# outputs.net
KiCad netlist of a schematic drawn in Altium Designer
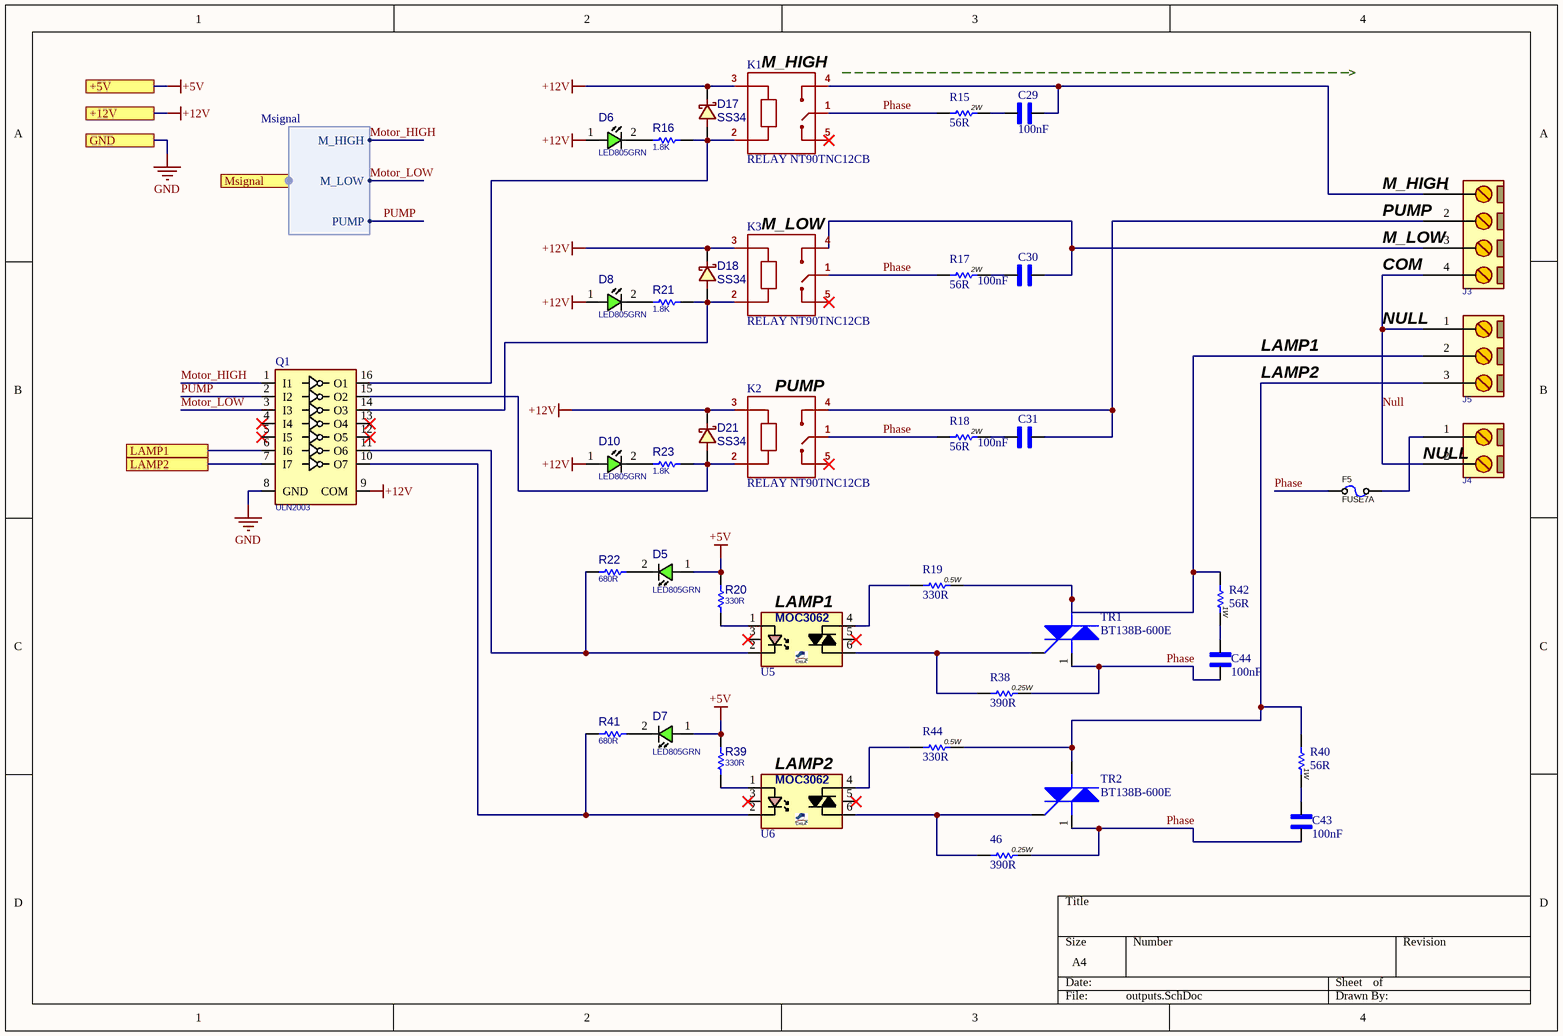
[diagram p0: outputs.SchDoc]

(export (version "E")
  (design (tool "Eeschema 10.0.6"))
  (components
    (comp (ref "46")
      (value "390R")
      (footprint "Res THD 0.25w")
      (description "Resistor 1/4W")
      (libsource (lib "Mehrdad") (part "Res THD 0.25w"))
    )
    (comp (ref "C29")
      (value "100nF")
      (footprint "Capacitor Film")
      (description "Capacitor Film Pitch=10mm")
      (libsource (lib "Mehrdad") (part "Capacitor Film"))
    )
    (comp (ref "C30")
      (value "100nF")
      (footprint "Capacitor Film")
      (description "Capacitor Film Pitch=10mm")
      (libsource (lib "Mehrdad") (part "Capacitor Film"))
    )
    (comp (ref "C31")
      (value "100nF")
      (footprint "Capacitor Film")
      (description "Capacitor Film Pitch=10mm")
      (libsource (lib "Mehrdad") (part "Capacitor Film"))
    )
    (comp (ref "C43")
      (value "100nF")
      (footprint "Capacitor Film")
      (description "Capacitor Film Pitch=10mm")
      (libsource (lib "") (part "Capacitor Film_1"))
    )
    (comp (ref "C44")
      (value "100nF")
      (footprint "Capacitor Film")
      (description "Capacitor Film Pitch=10mm")
      (libsource (lib "") (part "Capacitor Film_1"))
    )
    (comp (ref "D5")
      (value "LED805GRN")
      (footprint "LED0805GRN")
      (description "LED, SMD, 0805, GREEN")
      (libsource (lib "led(diode)") (part "LED_SMD_0805_GRN"))
    )
    (comp (ref "D6")
      (value "LED805GRN")
      (footprint "LED0805GRN")
      (description "LED, SMD, 0805, GREEN")
      (libsource (lib "led(diode)") (part "LED_SMD_0805_GRN"))
    )
    (comp (ref "D7")
      (value "LED805GRN")
      (footprint "LED0805GRN")
      (description "LED, SMD, 0805, GREEN")
      (libsource (lib "led(diode)") (part "LED_SMD_0805_GRN"))
    )
    (comp (ref "D8")
      (value "LED805GRN")
      (footprint "LED0805GRN")
      (description "LED, SMD, 0805, GREEN")
      (libsource (lib "led(diode)") (part "LED_SMD_0805_GRN"))
    )
    (comp (ref "D10")
      (value "LED805GRN")
      (footprint "LED0805GRN")
      (description "LED, SMD, 0805, GREEN")
      (libsource (lib "led(diode)") (part "LED_SMD_0805_GRN"))
    )
    (comp (ref "D17")
      (value "SS34")
      (footprint "D_SMB")
      (description "DIODE, SCHOTTKY, 20V, 3A")
      (fields (field (name "MANF") "VISHAY"))
      (libsource (lib "diode") (part "DIODE_SMD_SCHOTTKY_SS34"))
    )
    (comp (ref "D18")
      (value "SS34")
      (footprint "D_SMB")
      (description "DIODE, SCHOTTKY, 20V, 3A")
      (fields (field (name "MANF") "VISHAY"))
      (libsource (lib "diode") (part "DIODE_SMD_SCHOTTKY_SS34"))
    )
    (comp (ref "D21")
      (value "SS34")
      (footprint "D_SMB")
      (description "DIODE, SCHOTTKY, 20V, 3A")
      (fields (field (name "MANF") "VISHAY"))
      (libsource (lib "diode") (part "DIODE_SMD_SCHOTTKY_SS34"))
    )
    (comp (ref "F5")
      (value "FUSE7A")
      (footprint "FUSH_5X20MM")
      (description "Fuse HOLDER 5X20")
      (fields (field (name "MANF") "MANF") (field (name "MANF_P#") "MANF_PART#"))
      (libsource (lib "protect_tvs_esd_fuse") (part "FUSE_5X20"))
    )
    (comp (ref "J3")
      (value "CONN_GMSTB4")
      (footprint "GMSTB762_4")
      (description "CONN, PHOENIX MSTB, 5-G, 5.08mm pitch")
      (fields (field (name "MANF_P#") "GMSTB 2,5/4-G-7,62"))
      (libsource (lib "conn_power_terminalB") (part "CONN_GMSTB762_4"))
    )
    (comp (ref "J4")
      (value "CONN_GMSTB2")
      (footprint "GMSTB762_2")
      (description "CONN, PHOENIX GMSTB, 7.62mm pitch")
      (fields (field (name "MANF_P#") "GMSTB 2,5/2-G-7,62"))
      (libsource (lib "conn_power_terminalB") (part "CONN_GMSTB762_2"))
    )
    (comp (ref "J5")
      (value "CONN_GMSTB3")
      (footprint "GMSTB762_3")
      (description "CONN, PHOENIX MSTB, 5-G, 5.08mm pitch")
      (fields (field (name "MANF_P#") "GMSTB 2,5/3-G-7,62"))
      (libsource (lib "conn_power_terminalB") (part "CONN_GMSTB762_3"))
    )
    (comp (ref "K1")
      (value "RELAY NT90TNC12CB")
      (footprint "RELAY NT90TNC12CB")
      (description "Relay SPDT POWER NEEDLE")
      (fields (field (name "PUBLISHER") "Majid Derhambakhsh"))
      (libsource (lib "mBedLab Altium Library (2024-04-20)") (part "RELAY NT90TNC12CB"))
    )
    (comp (ref "K2")
      (value "RELAY NT90TNC12CB")
      (footprint "RELAY NT90TNC12CB")
      (description "Relay SPDT POWER NEEDLE")
      (fields (field (name "PUBLISHER") "Majid Derhambakhsh"))
      (libsource (lib "mBedLab Altium Library (2024-04-20)") (part "RELAY NT90TNC12CB"))
    )
    (comp (ref "K3")
      (value "RELAY NT90TNC12CB")
      (footprint "RELAY NT90TNC12CB")
      (description "Relay SPDT POWER NEEDLE")
      (fields (field (name "PUBLISHER") "Majid Derhambakhsh"))
      (libsource (lib "mBedLab Altium Library (2024-04-20)") (part "RELAY NT90TNC12CB"))
    )
    (comp (ref "Q1")
      (value "ULN2003")
      (footprint "SO_16")
      (description "Darlington, 7-CH, 50V, 0.5A, 5V TTL/CMOS")
      (fields (field (name "MANF_P#") "ULN2003D1") (field (name "MANF") "ST"))
      (libsource (lib "transistor_bjt") (part "ULN2003_SOP16_ST"))
    )
    (comp (ref "R15")
      (value "56R")
      (footprint "Res THD 2w")
      (description "Resistor 2W")
      (libsource (lib "Mehrdad") (part "Res THD 2w"))
    )
    (comp (ref "R16")
      (value "1.8K")
      (footprint "R0805")
      (description "RESISTOR, SMD")
      (libsource (lib "passive_smd") (part "RES_SMD_0805"))
    )
    (comp (ref "R17")
      (value "56R")
      (footprint "Res THD 2w")
      (description "Resistor 2W")
      (libsource (lib "Mehrdad") (part "Res THD 2w"))
    )
    (comp (ref "R18")
      (value "56R")
      (footprint "Res THD 2w")
      (description "Resistor 2W")
      (libsource (lib "Mehrdad") (part "Res THD 2w"))
    )
    (comp (ref "R19")
      (value "330R")
      (footprint "Res THD 0.5w")
      (description "Resistor 1/2W")
      (libsource (lib "Mehrdad") (part "Res THD 0.5w"))
    )
    (comp (ref "R20")
      (value "330R")
      (footprint "R0805")
      (description "RESISTOR, SMD")
      (libsource (lib "passive_smd") (part "RES_SMD_0805"))
    )
    (comp (ref "R21")
      (value "1.8K")
      (footprint "R0805")
      (description "RESISTOR, SMD")
      (libsource (lib "passive_smd") (part "RES_SMD_0805"))
    )
    (comp (ref "R22")
      (value "680R")
      (footprint "R0805")
      (description "RESISTOR, SMD")
      (libsource (lib "passive_smd") (part "RES_SMD_0805"))
    )
    (comp (ref "R23")
      (value "1.8K")
      (footprint "R0805")
      (description "RESISTOR, SMD")
      (libsource (lib "passive_smd") (part "RES_SMD_0805"))
    )
    (comp (ref "R38")
      (value "390R")
      (footprint "Res THD 0.25w")
      (description "Resistor 1/4W")
      (libsource (lib "Mehrdad") (part "Res THD 0.25w"))
    )
    (comp (ref "R39")
      (value "330R")
      (footprint "R0805")
      (description "RESISTOR, SMD")
      (libsource (lib "passive_smd") (part "RES_SMD_0805"))
    )
    (comp (ref "R40")
      (value "56R")
      (footprint "Res THD 1w")
      (description "Resistor 1W")
      (libsource (lib "Mehrdad") (part "Res THD 1w"))
    )
    (comp (ref "R41")
      (value "680R")
      (footprint "R0805")
      (description "RESISTOR, SMD")
      (libsource (lib "passive_smd") (part "RES_SMD_0805"))
    )
    (comp (ref "R42")
      (value "56R")
      (footprint "Res THD 1w")
      (description "Resistor 1W")
      (libsource (lib "Mehrdad") (part "Res THD 1w"))
    )
    (comp (ref "R44")
      (value "330R")
      (footprint "Res THD 0.5w")
      (description "Resistor 1/2W")
      (libsource (lib "Mehrdad") (part "Res THD 0.5w"))
    )
    (comp (ref "TR1")
      (value "BT138B-600E")
      (footprint "BT138B-600E")
      (description "Triac 600V, 12A")
      (libsource (lib "Mehrdad") (part "BT138B-600E"))
    )
    (comp (ref "TR2")
      (value "BT138B-600E")
      (footprint "BT138B-600E")
      (description "Triac 600V, 12A")
      (libsource (lib "Mehrdad") (part "BT138B-600E"))
    )
    (comp (ref "U5")
      (value "MOC3062")
      (footprint "DIP_6SMD")
      (description "OPTOTRIAC, 600v/1A, 6v In")
      (libsource (lib "optocoupler") (part "OPT_TRIAC6P_MOC3062SMD"))
    )
    (comp (ref "U6")
      (value "MOC3062")
      (footprint "DIP_6SMD")
      (description "OPTOTRIAC, 600v/1A, 6v In")
      (libsource (lib "optocoupler") (part "OPT_TRIAC6P_MOC3062SMD"))
    )
  )
  (nets
    (net (code "2") (name "+5V") (class "Default")
      (node (ref "D5") (pin "1") (pinfunction "ANODE_1") (pintype "passive"))
      (node (ref "D7") (pin "1") (pinfunction "ANODE_1") (pintype "passive"))
      (node (ref "R20") (pin "1") (pinfunction "1_1") (pintype "passive"))
      (node (ref "R39") (pin "1") (pinfunction "1_1") (pintype "passive"))
    )
    (net (code "3") (name "+12V") (class "Default")
      (node (ref "D10") (pin "1") (pinfunction "ANODE_1") (pintype "passive"))
      (node (ref "D17") (pin "2") (pinfunction "2_2") (pintype "passive"))
      (node (ref "D18") (pin "2") (pinfunction "2_2") (pintype "passive"))
      (node (ref "D21") (pin "2") (pinfunction "2_2") (pintype "passive"))
      (node (ref "D6") (pin "1") (pinfunction "ANODE_1") (pintype "passive"))
      (node (ref "D8") (pin "1") (pinfunction "ANODE_1") (pintype "passive"))
      (node (ref "K1") (pin "3") (pinfunction "A_3") (pintype "open_collector"))
      (node (ref "K2") (pin "3") (pinfunction "A_3") (pintype "open_collector"))
      (node (ref "K3") (pin "3") (pinfunction "A_3") (pintype "open_collector"))
      (node (ref "Q1") (pin "9") (pinfunction "COM_9") (pintype "passive"))
    )
    (net (code "4") (name "/LAMP1") (class "Default")
      (node (ref "Q1") (pin "6") (pinfunction "I6_6") (pintype "passive"))
    )
    (net (code "5") (name "/LAMP2") (class "Default")
      (node (ref "Q1") (pin "7") (pinfunction "I7_7") (pintype "passive"))
    )
    (net (code "6") (name "/Motor_HIGH") (class "Default")
      (node (ref "Q1") (pin "1") (pinfunction "I1_1") (pintype "passive"))
    )
    (net (code "7") (name "/Motor_LOW") (class "Default")
      (node (ref "Q1") (pin "3") (pinfunction "I3_3") (pintype "passive"))
    )
    (net (code "8") (name "/Null") (class "Default")
      (node (ref "J3") (pin "4") (pinfunction "4_4") (pintype "passive"))
      (node (ref "J4") (pin "2") (pinfunction "2_2") (pintype "passive"))
      (node (ref "J5") (pin "1") (pinfunction "1_1") (pintype "passive"))
    )
    (net (code "9") (name "/PUMP") (class "Default")
      (node (ref "Q1") (pin "2") (pinfunction "I2_2") (pintype "passive"))
    )
    (net (code "10") (name "/Phase") (class "Default")
      (node (ref "46") (pin "2") (pinfunction "2_2") (pintype "passive"))
      (node (ref "C43") (pin "2") (pinfunction "2_2") (pintype "passive"))
      (node (ref "C44") (pin "2") (pinfunction "2_2") (pintype "passive"))
      (node (ref "F5") (pin "1") (pinfunction "1_1") (pintype "passive"))
      (node (ref "K1") (pin "1") (pinfunction "COM_1") (pintype "open_collector"))
      (node (ref "K2") (pin "1") (pinfunction "COM_1") (pintype "open_collector"))
      (node (ref "K3") (pin "1") (pinfunction "COM_1") (pintype "open_collector"))
      (node (ref "R15") (pin "1") (pinfunction "1_1") (pintype "passive"))
      (node (ref "R17") (pin "1") (pinfunction "1_1") (pintype "passive"))
      (node (ref "R18") (pin "1") (pinfunction "1_1") (pintype "passive"))
      (node (ref "R38") (pin "2") (pinfunction "2_2") (pintype "passive"))
      (node (ref "TR1") (pin "1") (pinfunction "T1_1") (pintype "passive"))
      (node (ref "TR2") (pin "1") (pinfunction "T1_1") (pintype "passive"))
    )
    (net (code "12") (name "GND") (class "Default")
      (node (ref "Q1") (pin "8") (pinfunction "GND_8") (pintype "passive"))
    )
    (net (code "13") (name "Net-(C29-Pad1)") (class "Default")
      (node (ref "C29") (pin "1") (pinfunction "1_1") (pintype "passive"))
      (node (ref "R15") (pin "2") (pinfunction "2_2") (pintype "passive"))
    )
    (net (code "14") (name "Net-(C30-Pad1)") (class "Default")
      (node (ref "C30") (pin "1") (pinfunction "1_1") (pintype "passive"))
      (node (ref "R17") (pin "2") (pinfunction "2_2") (pintype "passive"))
    )
    (net (code "15") (name "Net-(C31-Pad1)") (class "Default")
      (node (ref "C31") (pin "1") (pinfunction "1_1") (pintype "passive"))
      (node (ref "R18") (pin "2") (pinfunction "2_2") (pintype "passive"))
    )
    (net (code "16") (name "Net-(C43-Pad1)") (class "Default")
      (node (ref "C43") (pin "1") (pinfunction "1_1") (pintype "passive"))
      (node (ref "R40") (pin "2") (pinfunction "2_2") (pintype "passive"))
    )
    (net (code "17") (name "Net-(C44-Pad1)") (class "Default")
      (node (ref "C44") (pin "1") (pinfunction "1_1") (pintype "passive"))
      (node (ref "R42") (pin "2") (pinfunction "2_2") (pintype "passive"))
    )
    (net (code "18") (name "Net-(D5-CATHODE)") (class "Default")
      (node (ref "D5") (pin "2") (pinfunction "CATHODE_2") (pintype "passive"))
      (node (ref "R22") (pin "1") (pinfunction "1_1") (pintype "passive"))
    )
    (net (code "19") (name "Net-(D6-CATHODE)") (class "Default")
      (node (ref "D6") (pin "2") (pinfunction "CATHODE_2") (pintype "passive"))
      (node (ref "R16") (pin "1") (pinfunction "1_1") (pintype "passive"))
    )
    (net (code "20") (name "Net-(D7-CATHODE)") (class "Default")
      (node (ref "D7") (pin "2") (pinfunction "CATHODE_2") (pintype "passive"))
      (node (ref "R41") (pin "1") (pinfunction "1_1") (pintype "passive"))
    )
    (net (code "21") (name "Net-(D8-CATHODE)") (class "Default")
      (node (ref "D8") (pin "2") (pinfunction "CATHODE_2") (pintype "passive"))
      (node (ref "R21") (pin "1") (pinfunction "1_1") (pintype "passive"))
    )
    (net (code "22") (name "Net-(D10-CATHODE)") (class "Default")
      (node (ref "D10") (pin "2") (pinfunction "CATHODE_2") (pintype "passive"))
      (node (ref "R23") (pin "1") (pinfunction "1_1") (pintype "passive"))
    )
    (net (code "23") (name "Net-(F5-Pad2)") (class "Default")
      (node (ref "F5") (pin "2") (pinfunction "2_2") (pintype "passive"))
      (node (ref "J4") (pin "1") (pinfunction "1_1") (pintype "passive"))
    )
    (net (code "24") (name "Net-(K1-N.O)") (class "Default")
      (node (ref "C29") (pin "2") (pinfunction "2_2") (pintype "passive"))
      (node (ref "J3") (pin "1") (pinfunction "1_1") (pintype "passive"))
      (node (ref "K1") (pin "4") (pinfunction "N.O_4") (pintype "open_collector"))
    )
    (net (code "25") (name "Net-(K2-N.O)") (class "Default")
      (node (ref "C31") (pin "2") (pinfunction "2_2") (pintype "passive"))
      (node (ref "J3") (pin "2") (pinfunction "2_2") (pintype "passive"))
      (node (ref "K2") (pin "4") (pinfunction "N.O_4") (pintype "open_collector"))
    )
    (net (code "26") (name "Net-(K3-N.O)") (class "Default")
      (node (ref "C30") (pin "2") (pinfunction "2_2") (pintype "passive"))
      (node (ref "J3") (pin "3") (pinfunction "3_3") (pintype "passive"))
      (node (ref "K3") (pin "4") (pinfunction "N.O_4") (pintype "open_collector"))
    )
    (net (code "27") (name "Net-(Q1-O1)") (class "Default")
      (node (ref "D17") (pin "1") (pinfunction "1_1") (pintype "passive"))
      (node (ref "K1") (pin "2") (pinfunction "A_2") (pintype "open_collector"))
      (node (ref "Q1") (pin "16") (pinfunction "O1_16") (pintype "passive"))
      (node (ref "R16") (pin "2") (pinfunction "2_2") (pintype "passive"))
    )
    (net (code "28") (name "Net-(Q1-O2)") (class "Default")
      (node (ref "D21") (pin "1") (pinfunction "1_1") (pintype "passive"))
      (node (ref "K2") (pin "2") (pinfunction "A_2") (pintype "open_collector"))
      (node (ref "Q1") (pin "15") (pinfunction "O2_15") (pintype "passive"))
      (node (ref "R23") (pin "2") (pinfunction "2_2") (pintype "passive"))
    )
    (net (code "29") (name "Net-(Q1-O3)") (class "Default")
      (node (ref "D18") (pin "1") (pinfunction "1_1") (pintype "passive"))
      (node (ref "K3") (pin "2") (pinfunction "A_2") (pintype "open_collector"))
      (node (ref "Q1") (pin "14") (pinfunction "O3_14") (pintype "passive"))
      (node (ref "R21") (pin "2") (pinfunction "2_2") (pintype "passive"))
    )
    (net (code "30") (name "Net-(Q1-O6)") (class "Default")
      (node (ref "Q1") (pin "11") (pinfunction "O6_11") (pintype "passive"))
      (node (ref "R22") (pin "2") (pinfunction "2_2") (pintype "passive"))
      (node (ref "U5") (pin "2") (pinfunction "K_2") (pintype "passive"))
    )
    (net (code "31") (name "Net-(Q1-O7)") (class "Default")
      (node (ref "Q1") (pin "10") (pinfunction "O7_10") (pintype "passive"))
      (node (ref "R41") (pin "2") (pinfunction "2_2") (pintype "passive"))
      (node (ref "U6") (pin "2") (pinfunction "K_2") (pintype "passive"))
    )
    (net (code "32") (name "Net-(R19-Pad1)") (class "Default")
      (node (ref "R19") (pin "1") (pinfunction "1_1") (pintype "passive"))
      (node (ref "U5") (pin "4") (pinfunction "A/K_4") (pintype "passive"))
    )
    (net (code "33") (name "Net-(R44-Pad1)") (class "Default")
      (node (ref "R44") (pin "1") (pinfunction "1_1") (pintype "passive"))
      (node (ref "U6") (pin "4") (pinfunction "A/K_4") (pintype "passive"))
    )
    (net (code "34") (name "Net-(TR1-G)") (class "Default")
      (node (ref "R38") (pin "1") (pinfunction "1_1") (pintype "passive"))
      (node (ref "TR1") (pin "3") (pinfunction "G_3") (pintype "passive"))
      (node (ref "U5") (pin "6") (pinfunction "A/K_6") (pintype "passive"))
    )
    (net (code "35") (name "Net-(TR1-T2)") (class "Default")
      (node (ref "J5") (pin "2") (pinfunction "2_2") (pintype "passive"))
      (node (ref "R19") (pin "2") (pinfunction "2_2") (pintype "passive"))
      (node (ref "R42") (pin "1") (pinfunction "1_1") (pintype "passive"))
      (node (ref "TR1") (pin "2_4") (pinfunction "T2_2_4") (pintype "passive"))
    )
    (net (code "36") (name "Net-(TR2-G)") (class "Default")
      (node (ref "46") (pin "1") (pinfunction "1_1") (pintype "passive"))
      (node (ref "TR2") (pin "3") (pinfunction "G_3") (pintype "passive"))
      (node (ref "U6") (pin "6") (pinfunction "A/K_6") (pintype "passive"))
    )
    (net (code "37") (name "Net-(TR2-T2)") (class "Default")
      (node (ref "J5") (pin "3") (pinfunction "3_3") (pintype "passive"))
      (node (ref "R40") (pin "1") (pinfunction "1_1") (pintype "passive"))
      (node (ref "R44") (pin "2") (pinfunction "2_2") (pintype "passive"))
      (node (ref "TR2") (pin "2_4") (pinfunction "T2_2_4") (pintype "passive"))
    )
    (net (code "38") (name "Net-(U5-A)") (class "Default")
      (node (ref "R20") (pin "2") (pinfunction "2_2") (pintype "passive"))
      (node (ref "U5") (pin "1") (pinfunction "A_1") (pintype "passive"))
    )
    (net (code "39") (name "Net-(U6-A)") (class "Default")
      (node (ref "R39") (pin "2") (pinfunction "2_2") (pintype "passive"))
      (node (ref "U6") (pin "1") (pinfunction "A_1") (pintype "passive"))
    )
    (net (code "40") (name "unconnected-(K1-N.C-Pad5)") (class "Default")
      (node (ref "K1") (pin "5") (pinfunction "N.C_5") (pintype "open_collector+no_connect"))
    )
    (net (code "41") (name "unconnected-(K2-N.C-Pad5)") (class "Default")
      (node (ref "K2") (pin "5") (pinfunction "N.C_5") (pintype "open_collector+no_connect"))
    )
    (net (code "42") (name "unconnected-(K3-N.C-Pad5)") (class "Default")
      (node (ref "K3") (pin "5") (pinfunction "N.C_5") (pintype "open_collector+no_connect"))
    )
    (net (code "43") (name "unconnected-(Q1-I4-Pad4)") (class "Default")
      (node (ref "Q1") (pin "4") (pinfunction "I4_4") (pintype "passive+no_connect"))
    )
    (net (code "44") (name "unconnected-(Q1-I5-Pad5)") (class "Default")
      (node (ref "Q1") (pin "5") (pinfunction "I5_5") (pintype "passive+no_connect"))
    )
    (net (code "45") (name "unconnected-(Q1-O4-Pad13)") (class "Default")
      (node (ref "Q1") (pin "13") (pinfunction "O4_13") (pintype "passive+no_connect"))
    )
    (net (code "46") (name "unconnected-(Q1-O5-Pad12)") (class "Default")
      (node (ref "Q1") (pin "12") (pinfunction "O5_12") (pintype "passive+no_connect"))
    )
    (net (code "47") (name "unconnected-(U5-NC-Pad3)") (class "Default")
      (node (ref "U5") (pin "3") (pinfunction "NC_3") (pintype "passive+no_connect"))
    )
    (net (code "48") (name "unconnected-(U5-NC-Pad5)") (class "Default")
      (node (ref "U5") (pin "5") (pinfunction "NC_5") (pintype "passive+no_connect"))
    )
    (net (code "49") (name "unconnected-(U6-NC-Pad3)") (class "Default")
      (node (ref "U6") (pin "3") (pinfunction "NC_3") (pintype "passive+no_connect"))
    )
    (net (code "50") (name "unconnected-(U6-NC-Pad5)") (class "Default")
      (node (ref "U6") (pin "5") (pinfunction "NC_5") (pintype "passive+no_connect"))
    )
  )
)
